# Adafruit_ISO1540.net
KiCad netlist of a schematic drawn in EAGLE
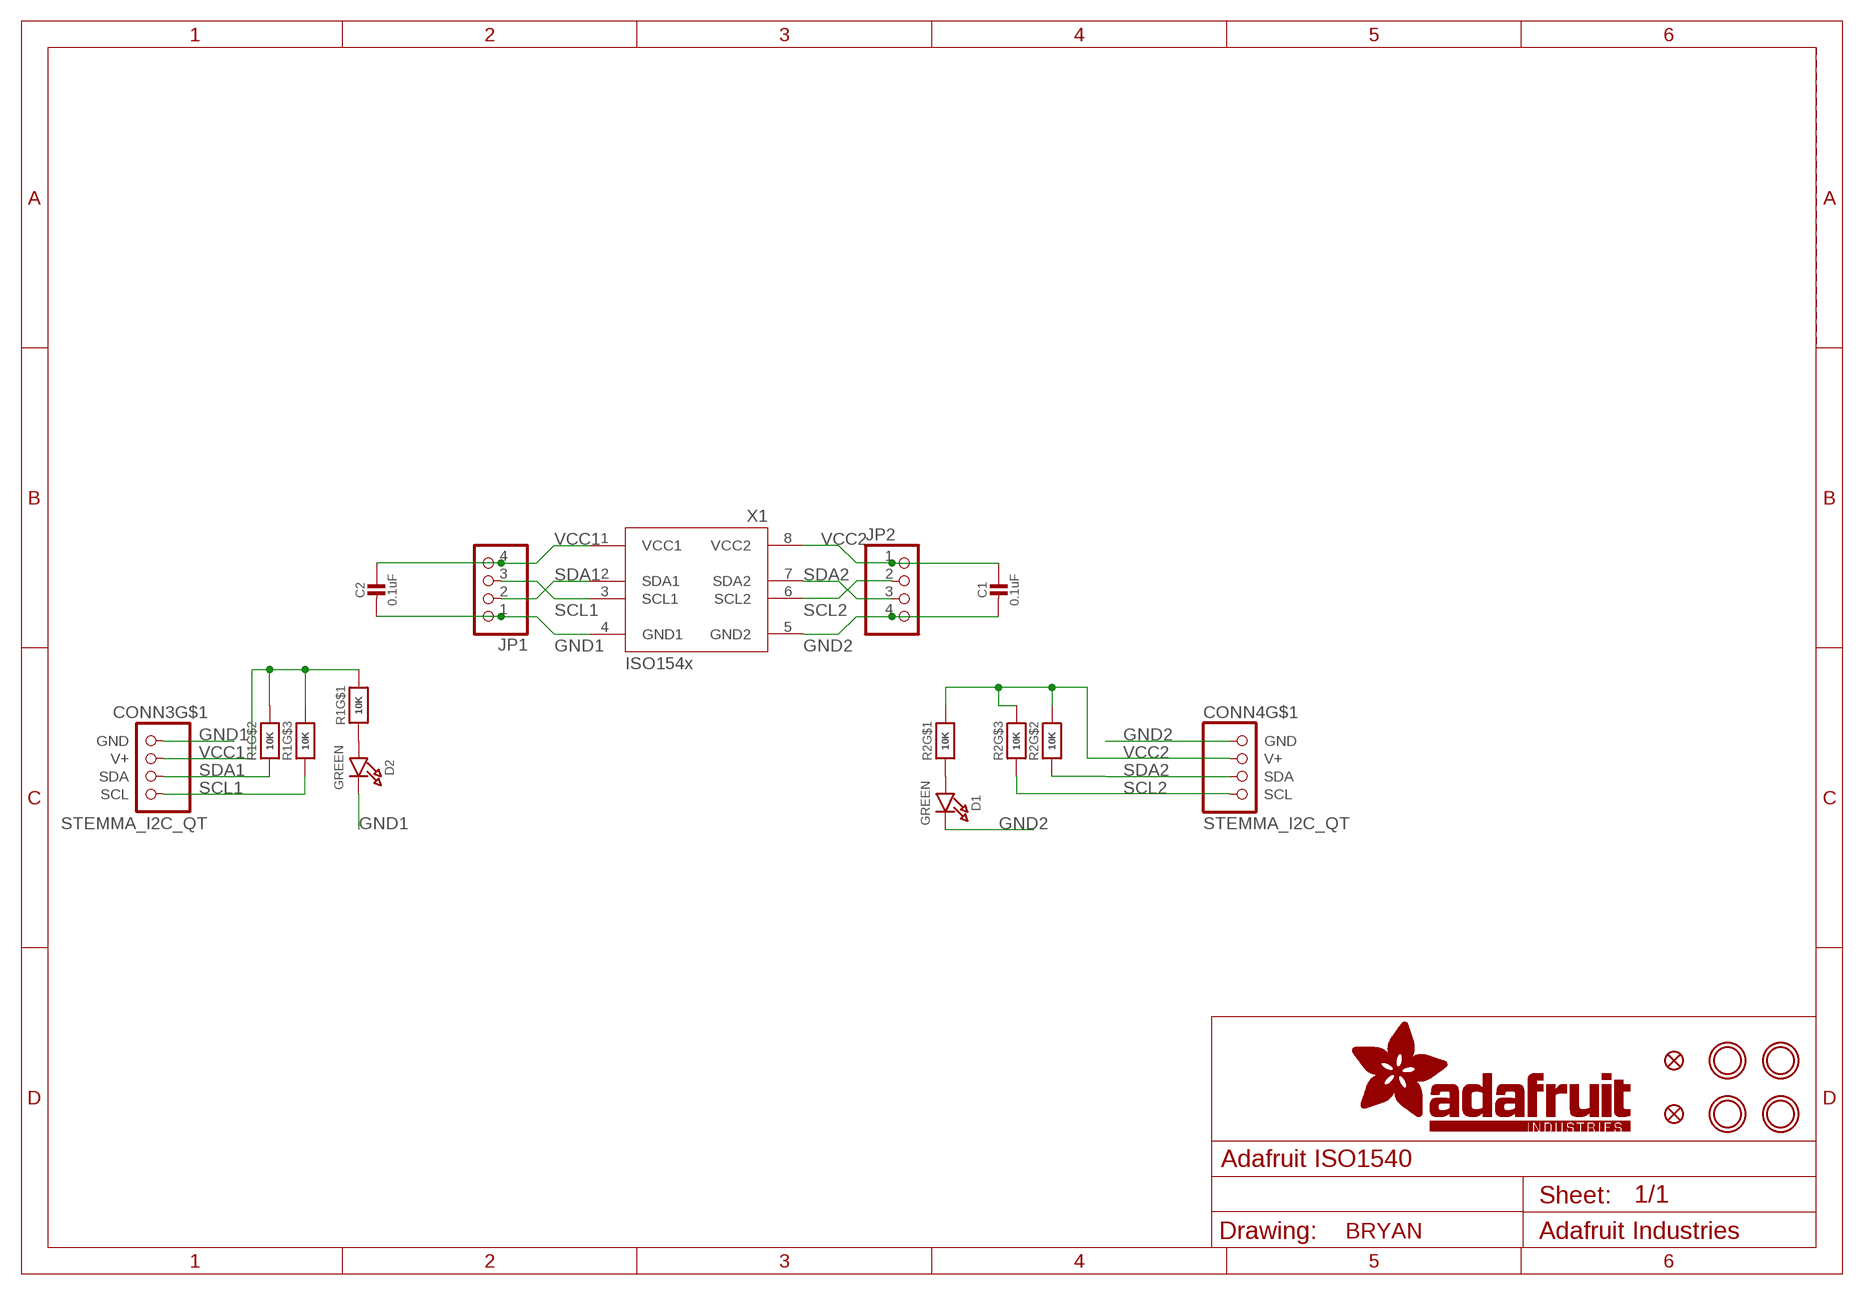
[diagram p0: schematic, sheet 1]

(export (version "E")
  (design (tool "Eeschema 10.0.6"))
  (components
    (comp (ref "C1")
      (value "0.1uF")
      (footprint "eagle-import:0603-NO")
      (libsource (lib "eagle-import") (part "CAP_CERAMIC0603_NO"))
    )
    (comp (ref "C2")
      (value "0.1uF")
      (footprint "eagle-import:0603-NO")
      (libsource (lib "eagle-import") (part "CAP_CERAMIC0603_NO"))
    )
    (comp (ref "CONN3")
      (value "STEMMA_I2C_QT")
      (footprint "eagle-import:JST_SH4")
      (libsource (lib "eagle-import") (part "STEMMA_I2C_QT"))
    )
    (comp (ref "CONN4")
      (value "STEMMA_I2C_QT")
      (footprint "eagle-import:JST_SH4")
      (libsource (lib "eagle-import") (part "STEMMA_I2C_QT"))
    )
    (comp (ref "D1")
      (value "GREEN")
      (footprint "eagle-import:CHIPLED_0603_NOOUTLINE")
      (libsource (lib "eagle-import") (part "LED0603_NOOUTLINE"))
    )
    (comp (ref "D2")
      (value "GREEN")
      (footprint "eagle-import:CHIPLED_0603_NOOUTLINE")
      (libsource (lib "eagle-import") (part "LED0603_NOOUTLINE"))
    )
    (comp (ref "FID3")
      (value "FIDUCIAL_1MM")
      (footprint "eagle-import:FIDUCIAL_1MM")
      (libsource (lib "eagle-import") (part "FIDUCIAL_1MM"))
    )
    (comp (ref "FID4")
      (value "FIDUCIAL_1MM")
      (footprint "eagle-import:FIDUCIAL_1MM")
      (libsource (lib "eagle-import") (part "FIDUCIAL_1MM"))
    )
    (comp (ref "JP1")
      (value "HEADER-1X4ROUND")
      (footprint "eagle-import:1X04_ROUND")
      (libsource (lib "eagle-import") (part "HEADER-1X4ROUND"))
    )
    (comp (ref "JP2")
      (value "HEADER-1X4ROUND")
      (footprint "eagle-import:1X04_ROUND")
      (libsource (lib "eagle-import") (part "HEADER-1X4ROUND"))
    )
    (comp (ref "R1")
      (value "10K")
      (footprint "eagle-import:RESPACK_4X0603")
      (libsource (lib "eagle-import") (part "RESISTOR_4PACK"))
    )
    (comp (ref "R2")
      (value "10K")
      (footprint "eagle-import:RESPACK_4X0603")
      (libsource (lib "eagle-import") (part "RESISTOR_4PACK"))
    )
    (comp (ref "U$1")
      (value "MOUNTINGHOLE2.5")
      (footprint "eagle-import:MOUNTINGHOLE_2.5_PLATED")
      (libsource (lib "eagle-import") (part "MOUNTINGHOLE2.5"))
    )
    (comp (ref "U$17")
      (value "MOUNTINGHOLE2.5")
      (footprint "eagle-import:MOUNTINGHOLE_2.5_PLATED")
      (libsource (lib "eagle-import") (part "MOUNTINGHOLE2.5"))
    )
    (comp (ref "U$19")
      (value "MOUNTINGHOLE2.5")
      (footprint "eagle-import:MOUNTINGHOLE_2.5_PLATED")
      (libsource (lib "eagle-import") (part "MOUNTINGHOLE2.5"))
    )
    (comp (ref "U$21")
      (value "MOUNTINGHOLE2.5")
      (footprint "eagle-import:MOUNTINGHOLE_2.5_PLATED")
      (libsource (lib "eagle-import") (part "MOUNTINGHOLE2.5"))
    )
    (comp (ref "X1")
      (value "ISO154X")
      (footprint "eagle-import:SOIC8_150MIL")
      (libsource (lib "eagle-import") (part "ISO154X"))
    )
  )
  (nets
    (net (code "1") (name "/GND1") (class "Default")
      (node (ref "C2") (pin "2") (pinfunction "2_2") (pintype "passive"))
      (node (ref "CONN3") (pin "1") (pinfunction "GND_1") (pintype "passive"))
      (node (ref "D2") (pin "C") (pinfunction "C_C") (pintype "passive"))
      (node (ref "JP1") (pin "1") (pinfunction "1_1") (pintype "passive"))
      (node (ref "X1") (pin "4") (pinfunction "GND1_4") (pintype "power_in"))
    )
    (net (code "2") (name "/GND2") (class "Default")
      (node (ref "C1") (pin "2") (pinfunction "2_2") (pintype "passive"))
      (node (ref "CONN4") (pin "1") (pinfunction "GND_1") (pintype "passive"))
      (node (ref "D1") (pin "C") (pinfunction "C_C") (pintype "passive"))
      (node (ref "JP2") (pin "4") (pinfunction "4_4") (pintype "passive"))
      (node (ref "X1") (pin "5") (pinfunction "GND2_5") (pintype "power_in"))
    )
    (net (code "3") (name "/SCL1") (class "Default")
      (node (ref "CONN3") (pin "4") (pinfunction "SCL_4") (pintype "passive"))
      (node (ref "JP1") (pin "3") (pinfunction "3_3") (pintype "passive"))
      (node (ref "R1") (pin "3") (pinfunction "1_3") (pintype "passive"))
      (node (ref "X1") (pin "3") (pinfunction "SCL1_3") (pintype "bidirectional"))
    )
    (net (code "4") (name "/SCL2") (class "Default")
      (node (ref "CONN4") (pin "4") (pinfunction "SCL_4") (pintype "passive"))
      (node (ref "JP2") (pin "2") (pinfunction "2_2") (pintype "passive"))
      (node (ref "R2") (pin "3") (pinfunction "1_3") (pintype "passive"))
      (node (ref "X1") (pin "6") (pinfunction "SCL2_6") (pintype "bidirectional"))
    )
    (net (code "5") (name "/SDA1") (class "Default")
      (node (ref "CONN3") (pin "3") (pinfunction "SDA_3") (pintype "passive"))
      (node (ref "JP1") (pin "2") (pinfunction "2_2") (pintype "passive"))
      (node (ref "R1") (pin "2") (pinfunction "1_2") (pintype "passive"))
      (node (ref "X1") (pin "2") (pinfunction "SDA1_2") (pintype "bidirectional"))
    )
    (net (code "6") (name "/SDA2") (class "Default")
      (node (ref "CONN4") (pin "3") (pinfunction "SDA_3") (pintype "passive"))
      (node (ref "JP2") (pin "3") (pinfunction "3_3") (pintype "passive"))
      (node (ref "R2") (pin "2") (pinfunction "1_2") (pintype "passive"))
      (node (ref "X1") (pin "7") (pinfunction "SDA2_7") (pintype "bidirectional"))
    )
    (net (code "7") (name "/VCC1") (class "Default")
      (node (ref "C2") (pin "1") (pinfunction "1_1") (pintype "passive"))
      (node (ref "CONN3") (pin "2") (pinfunction "V+_2") (pintype "passive"))
      (node (ref "JP1") (pin "4") (pinfunction "4_4") (pintype "passive"))
      (node (ref "R1") (pin "6") (pinfunction "2_6") (pintype "passive"))
      (node (ref "R1") (pin "7") (pinfunction "2_7") (pintype "passive"))
      (node (ref "R1") (pin "8") (pinfunction "2_8") (pintype "passive"))
      (node (ref "X1") (pin "1") (pinfunction "VCC1_1") (pintype "power_in"))
    )
    (net (code "8") (name "/VCC2") (class "Default")
      (node (ref "C1") (pin "1") (pinfunction "1_1") (pintype "passive"))
      (node (ref "CONN4") (pin "2") (pinfunction "V+_2") (pintype "passive"))
      (node (ref "JP2") (pin "1") (pinfunction "1_1") (pintype "passive"))
      (node (ref "R2") (pin "6") (pinfunction "2_6") (pintype "passive"))
      (node (ref "R2") (pin "7") (pinfunction "2_7") (pintype "passive"))
      (node (ref "R2") (pin "8") (pinfunction "2_8") (pintype "passive"))
      (node (ref "X1") (pin "8") (pinfunction "VCC2_8") (pintype "power_in"))
    )
    (net (code "9") (name "Net-(D1-PadA)") (class "Default")
      (node (ref "D1") (pin "A") (pinfunction "A_A") (pintype "passive"))
      (node (ref "R2") (pin "1") (pinfunction "1_1") (pintype "passive"))
    )
    (net (code "10") (name "Net-(D2-PadA)") (class "Default")
      (node (ref "D2") (pin "A") (pinfunction "A_A") (pintype "passive"))
      (node (ref "R1") (pin "1") (pinfunction "1_1") (pintype "passive"))
    )
  )
)
